# design.net
KiCad netlist of a schematic drawn in Altium Designer
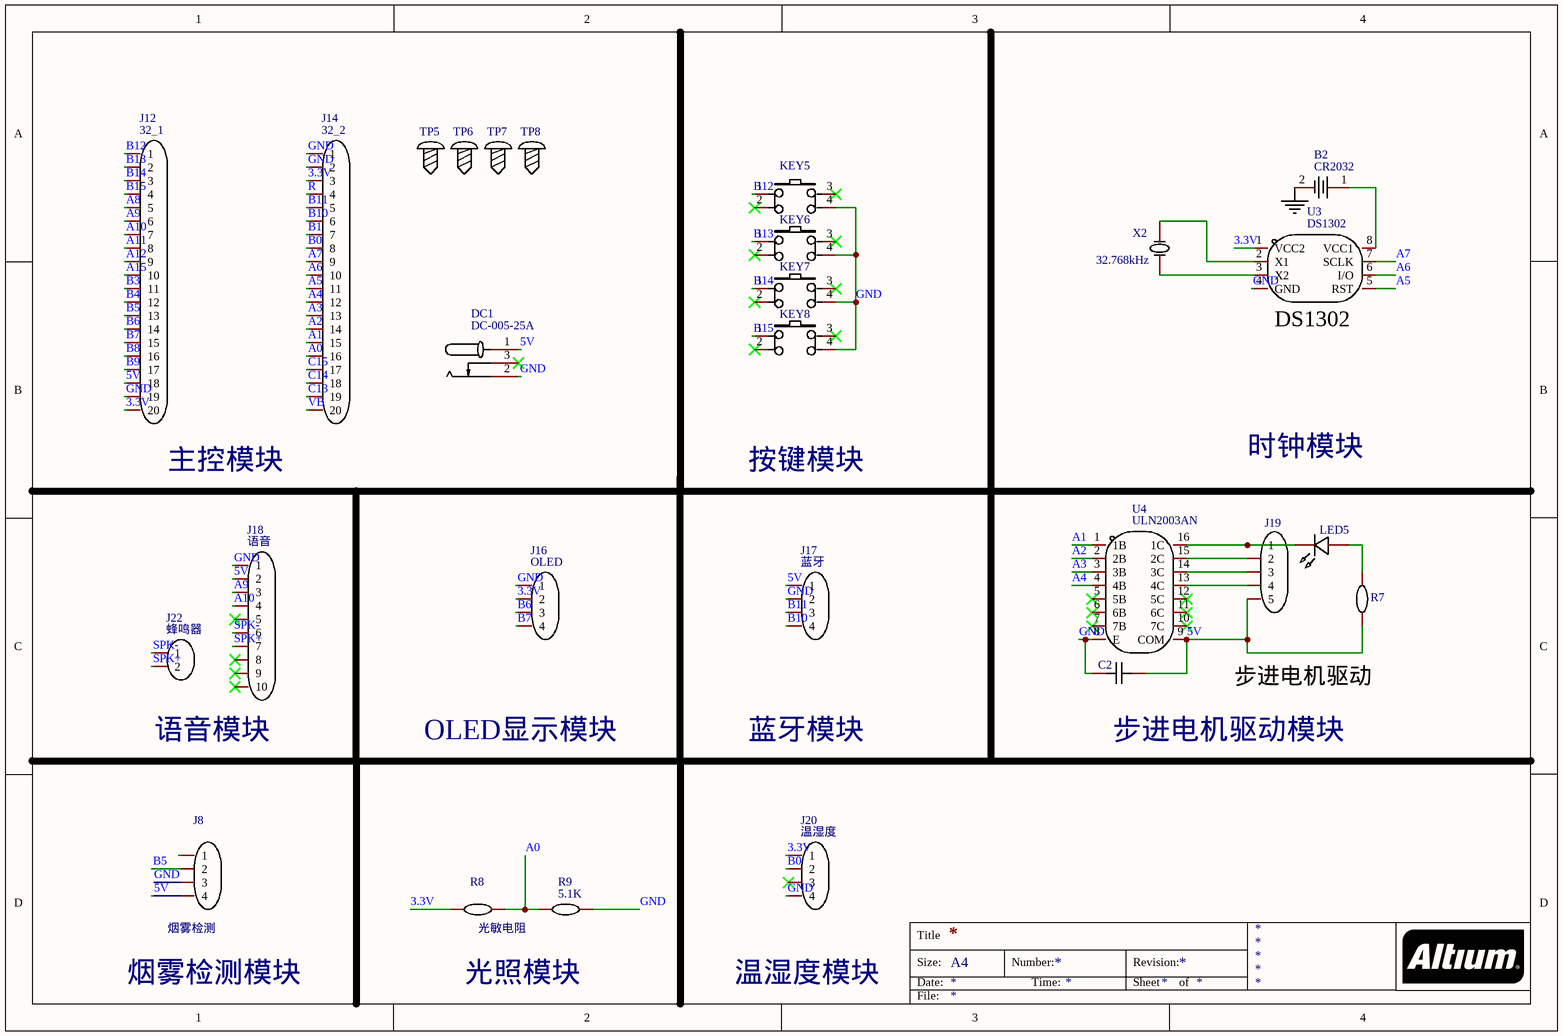
[diagram p0: 智能窗帘.schdoc]

(export (version "E")
  (design (tool "Eeschema 10.0.6"))
  (components
    (comp (ref "B2")
      (value "CR2032")
      (footprint "BAT-TH_BS-2-1")
      (fields
        (field (name "NAME") "CR2032")
        (field (name "MANUFACTURER") "Q&J")
        (field (name "MANUFACTURER PART") "BS-2-1")
      )
      (libsource (lib "altium-import") (part "root_2_BS-2-1_"))
    )
    (comp (ref "C2")
      (value "100nF")
      (footprint "CAP-TH_L5.5-W2.5-P5.00-D1.0")
      (fields
        (field (name "MANUFACTURER") "SHM(南方宏明)")
        (field (name "MANUFACTURER PART") "CCT104KC6X7RF5FH5A0")
      )
      (libsource (lib "altium-import") (part "root_0_CCT104KC6X7RF5FH5A0_"))
    )
    (comp (ref "DC1")
      (value "DC-005-25A")
      (footprint "DC-IN-TH_DC005")
      (fields (field (name "NAME") "DC-005-25A") (field (name "MANUFACTURER") "HRO"))
      (libsource (lib "altium-import") (part "root_0_DC-005-25A_"))
    )
    (comp (ref "J8")
      (value "温湿度")
      (footprint "HDR-M-2.54_1X4")
      (fields (field (name "NAME") "烟雾检测"))
      (libsource (lib "altium-import") (part "root_0_温湿度_"))
    )
    (comp (ref "J12")
      (value "32_1")
      (footprint "HDR-M-2.54_1X20")
      (fields (field (name "NAME") "32_1"))
      (libsource (lib "altium-import") (part "root_0_32_1_"))
    )
    (comp (ref "J14")
      (value "32_2")
      (footprint "HDR-M-2.54_1X20")
      (fields (field (name "NAME") "32_2"))
      (libsource (lib "altium-import") (part "root_0_32_2_"))
    )
    (comp (ref "J16")
      (value "OLED")
      (footprint "HDR-M-2.54_1X4")
      (fields (field (name "NAME") "OLED"))
      (libsource (lib "altium-import") (part "root_0_OLED_"))
    )
    (comp (ref "J17")
      (value "蓝牙")
      (footprint "HDR-M-2.54_1X4")
      (fields (field (name "NAME") "蓝牙"))
      (libsource (lib "altium-import") (part "root_0_蓝牙_"))
    )
    (comp (ref "J18")
      (value "语音")
      (footprint "HDR-M-2.54_1X10")
      (fields (field (name "NAME") "语音"))
      (libsource (lib "altium-import") (part "root_0_语音_"))
    )
    (comp (ref "J19")
      (value "HDR-M-2.54_1x5")
      (footprint "HDR-M-2.54_1X5")
      (libsource (lib "altium-import") (part "root_0_HDR-M-2.54_1x5_"))
    )
    (comp (ref "J20")
      (value "温湿度")
      (footprint "HDR-M-2.54_1X4")
      (fields (field (name "NAME") "温湿度"))
      (libsource (lib "altium-import") (part "root_0_温湿度_"))
    )
    (comp (ref "J22")
      (value "蜂鸣器")
      (footprint "HDR-M-2.54_1X2")
      (fields (field (name "NAME") "蜂鸣器"))
      (libsource (lib "altium-import") (part "root_0_蜂鸣器_"))
    )
    (comp (ref "KEY5")
      (value "6*6*9")
      (footprint "KEY-TH_4P-L6.0-W6.0-P4.50")
      (fields (field (name "MANUFACTURER") "ReliaPro"))
      (libsource (lib "altium-import") (part "root_0_6*6*9_"))
    )
    (comp (ref "KEY6")
      (value "6*6*9")
      (footprint "KEY-TH_4P-L6.0-W6.0-P4.50")
      (fields (field (name "MANUFACTURER") "ReliaPro"))
      (libsource (lib "altium-import") (part "root_0_6*6*9_"))
    )
    (comp (ref "KEY7")
      (value "6*6*9")
      (footprint "KEY-TH_4P-L6.0-W6.0-P4.50")
      (fields (field (name "MANUFACTURER") "ReliaPro"))
      (libsource (lib "altium-import") (part "root_0_6*6*9_"))
    )
    (comp (ref "KEY8")
      (value "6*6*9")
      (footprint "KEY-TH_4P-L6.0-W6.0-P4.50")
      (fields (field (name "MANUFACTURER") "ReliaPro"))
      (libsource (lib "altium-import") (part "root_0_6*6*9_"))
    )
    (comp (ref "LED5")
      (value "LED-TH-3mm_R")
      (footprint "LED-TH_BD3.0_RED")
      (fields
        (field (name "MANUFACTURER") "EVERLIGHT(台湾亿光)")
        (field (name "MANUFACTURER PART") "204-10SDRD/S530-A3-L")
      )
      (libsource (lib "altium-import") (part "root_2_204-10SDRD/S530-A3-L_"))
    )
    (comp (ref "R7")
      (value "0.5")
      (footprint "RES-TH_BD1.9-L3.3-P7.30-D0.5")
      (fields (field (name "MANUFACTURER") "CCO") (field (name "MANUFACTURER PART") "CF1/6W-0.5Ω±5% T52"))
      (libsource (lib "altium-import") (part "root_3_CF1/6W-0.5Ω±5% T52_"))
    )
    (comp (ref "R8")
      (value "光敏电阻")
      (footprint "RES-TH_BD2.5-L4.7-P8.70-D0.5")
      (fields
        (field (name "NAME") "光敏电阻")
        (field (name "MANUFACTURER") "TA-I Tech")
        (field (name "MANUFACTURER PART") "RN16T51001F")
      )
      (libsource (lib "altium-import") (part "root_0_RN16T51001F_"))
    )
    (comp (ref "R9")
      (value "5.1K")
      (footprint "RES-TH_BD2.5-L4.7-P8.70-D0.5")
      (fields
        (field (name "NAME") "5.1K")
        (field (name "MANUFACTURER") "TA-I Tech")
        (field (name "MANUFACTURER PART") "RN16T51001F")
      )
      (libsource (lib "altium-import") (part "root_0_RN16T51001F_"))
    )
    (comp (ref "TP5")
      (value "M3x6+4")
      (footprint "M3铜柱")
      (libsource (lib "altium-import") (part "root_0_M3x6+4_"))
    )
    (comp (ref "TP6")
      (value "M3x6+4")
      (footprint "M3铜柱")
      (libsource (lib "altium-import") (part "root_0_M3x6+4_"))
    )
    (comp (ref "TP7")
      (value "M3x6+4")
      (footprint "M3铜柱")
      (libsource (lib "altium-import") (part "root_0_M3x6+4_"))
    )
    (comp (ref "TP8")
      (value "M3x6+4")
      (footprint "M3铜柱")
      (libsource (lib "altium-import") (part "root_0_M3x6+4_"))
    )
    (comp (ref "U3")
      (value "DS1302")
      (footprint "DIP-8_L9.7-W6.4-P2.54-LS7.6-BL")
      (fields
        (field (name "NAME") "DS1302")
        (field (name "MANUFACTURER") "HGSEMI")
        (field (name "MANUFACTURER PART") "DS1302N")
      )
      (libsource (lib "altium-import") (part "root_0_DS1302N_"))
    )
    (comp (ref "U4")
      (value "ULN2003AN")
      (footprint "DIP-16_L19.8-W6.5-P2.54-LS7.6-BL")
      (fields (field (name "NAME") "ULN2003AN") (field (name "MANUFACTURER") "HTC Korea TAEJIN Tech"))
      (libsource (lib "altium-import") (part "root_0_ULN2003AN_"))
    )
    (comp (ref "X2")
      (value "32.768kHz")
      (footprint "OSC-TH_BD2.0-P0.70-D0.3")
      (fields
        (field (name "NAME") "32.768kHz")
        (field (name "MANUFACTURER") "LIMING(利明)")
        (field (name "MANUFACTURER PART") "26S-32.768-12.5-10-10/B")
      )
      (libsource (lib "altium-import") (part "root_1_26S-32.768-12.5-10-10/B_"))
    )
  )
  (nets
    (net (code "1") (name "/3.3V") (class "Default")
      (node (ref "J12") (pin "20") (pinfunction "20_20") (pintype "passive"))
      (node (ref "J14") (pin "3") (pinfunction "3_3") (pintype "passive"))
      (node (ref "J16") (pin "2") (pinfunction "2_2") (pintype "passive"))
      (node (ref "J20") (pin "1") (pinfunction "1_1") (pintype "passive"))
      (node (ref "R8") (pin "1") (pinfunction "1_1") (pintype "passive"))
      (node (ref "U3") (pin "1") (pinfunction "VCC2_1") (pintype "passive"))
    )
    (net (code "2") (name "/5V") (class "Default")
      (node (ref "C2") (pin "2") (pinfunction "2_2") (pintype "passive"))
      (node (ref "DC1") (pin "1") (pinfunction "1_1") (pintype "passive"))
      (node (ref "J12") (pin "18") (pinfunction "18_18") (pintype "passive"))
      (node (ref "J17") (pin "1") (pinfunction "1_1") (pintype "passive"))
      (node (ref "J18") (pin "2") (pinfunction "2_2") (pintype "passive"))
      (node (ref "J19") (pin "5") (pinfunction "5_5") (pintype "passive"))
      (node (ref "J8") (pin "4") (pinfunction "4_4") (pintype "passive"))
      (node (ref "R7") (pin "2") (pinfunction "2_2") (pintype "passive"))
      (node (ref "U4") (pin "9") (pinfunction "COM_9") (pintype "passive"))
    )
    (net (code "3") (name "/A0") (class "Default")
      (node (ref "J14") (pin "16") (pinfunction "16_16") (pintype "passive"))
      (node (ref "R8") (pin "2") (pinfunction "2_2") (pintype "passive"))
      (node (ref "R9") (pin "1") (pinfunction "1_1") (pintype "passive"))
    )
    (net (code "4") (name "/A1") (class "Default")
      (node (ref "J14") (pin "15") (pinfunction "15_15") (pintype "passive"))
      (node (ref "U4") (pin "1") (pinfunction "1B_1") (pintype "passive"))
    )
    (net (code "5") (name "/A2") (class "Default")
      (node (ref "J14") (pin "14") (pinfunction "14_14") (pintype "passive"))
      (node (ref "U4") (pin "2") (pinfunction "2B_2") (pintype "passive"))
    )
    (net (code "6") (name "/A3") (class "Default")
      (node (ref "J14") (pin "13") (pinfunction "13_13") (pintype "passive"))
      (node (ref "U4") (pin "3") (pinfunction "3B_3") (pintype "passive"))
    )
    (net (code "7") (name "/A4") (class "Default")
      (node (ref "J14") (pin "12") (pinfunction "12_12") (pintype "passive"))
      (node (ref "U4") (pin "4") (pinfunction "4B_4") (pintype "passive"))
    )
    (net (code "8") (name "/A5") (class "Default")
      (node (ref "J14") (pin "11") (pinfunction "11_11") (pintype "passive"))
      (node (ref "U3") (pin "5") (pinfunction "RST_5") (pintype "passive"))
    )
    (net (code "9") (name "/A6") (class "Default")
      (node (ref "J14") (pin "10") (pinfunction "10_10") (pintype "passive"))
      (node (ref "U3") (pin "6") (pinfunction "I/O_6") (pintype "passive"))
    )
    (net (code "10") (name "/A7") (class "Default")
      (node (ref "J14") (pin "9") (pinfunction "9_9") (pintype "passive"))
      (node (ref "U3") (pin "7") (pinfunction "SCLK_7") (pintype "passive"))
    )
    (net (code "11") (name "/A8") (class "Default")
      (node (ref "J12") (pin "5") (pinfunction "5_5") (pintype "passive"))
    )
    (net (code "12") (name "/A9") (class "Default")
      (node (ref "J12") (pin "6") (pinfunction "6_6") (pintype "passive"))
      (node (ref "J18") (pin "3") (pinfunction "3_3") (pintype "passive"))
    )
    (net (code "13") (name "/A10") (class "Default")
      (node (ref "J12") (pin "7") (pinfunction "7_7") (pintype "passive"))
      (node (ref "J18") (pin "4") (pinfunction "4_4") (pintype "passive"))
    )
    (net (code "14") (name "/A11") (class "Default")
      (node (ref "J12") (pin "8") (pinfunction "8_8") (pintype "passive"))
    )
    (net (code "15") (name "/A12") (class "Default")
      (node (ref "J12") (pin "9") (pinfunction "9_9") (pintype "passive"))
    )
    (net (code "16") (name "/A15") (class "Default")
      (node (ref "J12") (pin "10") (pinfunction "10_10") (pintype "passive"))
    )
    (net (code "17") (name "/B0") (class "Default")
      (node (ref "J14") (pin "8") (pinfunction "8_8") (pintype "passive"))
      (node (ref "J20") (pin "2") (pinfunction "2_2") (pintype "passive"))
    )
    (net (code "18") (name "/B1") (class "Default")
      (node (ref "J14") (pin "7") (pinfunction "7_7") (pintype "passive"))
    )
    (net (code "19") (name "/B3") (class "Default")
      (node (ref "J12") (pin "11") (pinfunction "11_11") (pintype "passive"))
    )
    (net (code "20") (name "/B4") (class "Default")
      (node (ref "J12") (pin "12") (pinfunction "12_12") (pintype "passive"))
    )
    (net (code "21") (name "/B5") (class "Default")
      (node (ref "J12") (pin "13") (pinfunction "13_13") (pintype "passive"))
      (node (ref "J8") (pin "2") (pinfunction "2_2") (pintype "passive"))
    )
    (net (code "22") (name "/B6") (class "Default")
      (node (ref "J12") (pin "14") (pinfunction "14_14") (pintype "passive"))
      (node (ref "J16") (pin "3") (pinfunction "3_3") (pintype "passive"))
    )
    (net (code "23") (name "/B7") (class "Default")
      (node (ref "J12") (pin "15") (pinfunction "15_15") (pintype "passive"))
      (node (ref "J16") (pin "4") (pinfunction "4_4") (pintype "passive"))
    )
    (net (code "24") (name "/B8") (class "Default")
      (node (ref "J12") (pin "16") (pinfunction "16_16") (pintype "passive"))
    )
    (net (code "25") (name "/B9") (class "Default")
      (node (ref "J12") (pin "17") (pinfunction "17_17") (pintype "passive"))
    )
    (net (code "26") (name "/B10") (class "Default")
      (node (ref "J14") (pin "6") (pinfunction "6_6") (pintype "passive"))
      (node (ref "J17") (pin "4") (pinfunction "4_4") (pintype "passive"))
    )
    (net (code "27") (name "/B11") (class "Default")
      (node (ref "J14") (pin "5") (pinfunction "5_5") (pintype "passive"))
      (node (ref "J17") (pin "3") (pinfunction "3_3") (pintype "passive"))
    )
    (net (code "28") (name "/B12") (class "Default")
      (node (ref "J12") (pin "1") (pinfunction "1_1") (pintype "passive"))
      (node (ref "KEY5") (pin "1") (pinfunction "1_1") (pintype "passive"))
    )
    (net (code "29") (name "/B13") (class "Default")
      (node (ref "J12") (pin "2") (pinfunction "2_2") (pintype "passive"))
      (node (ref "KEY6") (pin "1") (pinfunction "1_1") (pintype "passive"))
    )
    (net (code "30") (name "/B14") (class "Default")
      (node (ref "J12") (pin "3") (pinfunction "3_3") (pintype "passive"))
      (node (ref "KEY7") (pin "1") (pinfunction "1_1") (pintype "passive"))
    )
    (net (code "31") (name "/B15") (class "Default")
      (node (ref "J12") (pin "4") (pinfunction "4_4") (pintype "passive"))
      (node (ref "KEY8") (pin "1") (pinfunction "1_1") (pintype "passive"))
    )
    (net (code "32") (name "/C13") (class "Default")
      (node (ref "J14") (pin "19") (pinfunction "19_19") (pintype "passive"))
    )
    (net (code "33") (name "/C14") (class "Default")
      (node (ref "J14") (pin "18") (pinfunction "18_18") (pintype "passive"))
    )
    (net (code "34") (name "/C15") (class "Default")
      (node (ref "J14") (pin "17") (pinfunction "17_17") (pintype "passive"))
    )
    (net (code "35") (name "/R") (class "Default")
      (node (ref "J14") (pin "4") (pinfunction "4_4") (pintype "passive"))
    )
    (net (code "36") (name "/SPK+") (class "Default")
      (node (ref "J18") (pin "7") (pinfunction "7_7") (pintype "passive"))
      (node (ref "J22") (pin "2") (pinfunction "2_2") (pintype "passive"))
    )
    (net (code "37") (name "/SPK-") (class "Default")
      (node (ref "J18") (pin "6") (pinfunction "6_6") (pintype "passive"))
      (node (ref "J22") (pin "1") (pinfunction "1_1") (pintype "passive"))
    )
    (net (code "38") (name "/VB") (class "Default")
      (node (ref "J14") (pin "20") (pinfunction "20_20") (pintype "passive"))
    )
    (net (code "39") (name "GND") (class "Default")
      (node (ref "B2") (pin "2") (pinfunction "2_2") (pintype "passive"))
      (node (ref "C2") (pin "1") (pinfunction "1_1") (pintype "passive"))
      (node (ref "DC1") (pin "2") (pinfunction "2_2") (pintype "passive"))
      (node (ref "J12") (pin "19") (pinfunction "19_19") (pintype "passive"))
      (node (ref "J14") (pin "1") (pinfunction "1_1") (pintype "passive"))
      (node (ref "J14") (pin "2") (pinfunction "2_2") (pintype "passive"))
      (node (ref "J16") (pin "1") (pinfunction "1_1") (pintype "passive"))
      (node (ref "J17") (pin "2") (pinfunction "2_2") (pintype "passive"))
      (node (ref "J18") (pin "1") (pinfunction "1_1") (pintype "passive"))
      (node (ref "J20") (pin "4") (pinfunction "4_4") (pintype "passive"))
      (node (ref "J8") (pin "3") (pinfunction "3_3") (pintype "passive"))
      (node (ref "KEY5") (pin "4") (pinfunction "4_4") (pintype "passive"))
      (node (ref "KEY6") (pin "4") (pinfunction "4_4") (pintype "passive"))
      (node (ref "KEY7") (pin "4") (pinfunction "4_4") (pintype "passive"))
      (node (ref "KEY8") (pin "4") (pinfunction "4_4") (pintype "passive"))
      (node (ref "R9") (pin "2") (pinfunction "2_2") (pintype "passive"))
      (node (ref "U3") (pin "4") (pinfunction "GND_4") (pintype "passive"))
      (node (ref "U4") (pin "8") (pinfunction "E_8") (pintype "passive"))
    )
    (net (code "40") (name "Net-(LED5-Pad1)") (class "Default")
      (node (ref "LED5") (pin "1") (pinfunction "1_1") (pintype "passive"))
      (node (ref "R7") (pin "1") (pinfunction "1_1") (pintype "passive"))
    )
    (net (code "41") (name "Net-(U3-VCC1)") (class "Default")
      (node (ref "B2") (pin "1") (pinfunction "1_1") (pintype "passive"))
      (node (ref "U3") (pin "8") (pinfunction "VCC1_8") (pintype "passive"))
    )
    (net (code "42") (name "Net-(U3-X1)") (class "Default")
      (node (ref "U3") (pin "2") (pinfunction "X1_2") (pintype "passive"))
      (node (ref "X2") (pin "2") (pinfunction "OSC2_2") (pintype "passive"))
    )
    (net (code "43") (name "Net-(U3-X2)") (class "Default")
      (node (ref "U3") (pin "3") (pinfunction "X2_3") (pintype "passive"))
      (node (ref "X2") (pin "1") (pinfunction "OSC1_1") (pintype "passive"))
    )
    (net (code "44") (name "Net-(U4-1C)") (class "Default")
      (node (ref "J19") (pin "1") (pinfunction "1_1") (pintype "passive"))
      (node (ref "LED5") (pin "2") (pinfunction "2_2") (pintype "passive"))
      (node (ref "U4") (pin "16") (pinfunction "1C_16") (pintype "passive"))
    )
    (net (code "45") (name "Net-(U4-2C)") (class "Default")
      (node (ref "J19") (pin "2") (pinfunction "2_2") (pintype "passive"))
      (node (ref "U4") (pin "15") (pinfunction "2C_15") (pintype "passive"))
    )
    (net (code "46") (name "Net-(U4-3C)") (class "Default")
      (node (ref "J19") (pin "3") (pinfunction "3_3") (pintype "passive"))
      (node (ref "U4") (pin "14") (pinfunction "3C_14") (pintype "passive"))
    )
    (net (code "47") (name "Net-(U4-4C)") (class "Default")
      (node (ref "J19") (pin "4") (pinfunction "4_4") (pintype "passive"))
      (node (ref "U4") (pin "13") (pinfunction "4C_13") (pintype "passive"))
    )
    (net (code "48") (name "unconnected-(DC1-Pad3)") (class "Default")
      (node (ref "DC1") (pin "3") (pinfunction "3_3") (pintype "passive+no_connect"))
    )
    (net (code "49") (name "unconnected-(J8-Pad1)") (class "Default")
      (node (ref "J8") (pin "1") (pinfunction "1_1") (pintype "passive"))
    )
    (net (code "50") (name "unconnected-(J18-Pad5)") (class "Default")
      (node (ref "J18") (pin "5") (pinfunction "5_5") (pintype "passive+no_connect"))
    )
    (net (code "51") (name "unconnected-(J18-Pad8)") (class "Default")
      (node (ref "J18") (pin "8") (pinfunction "8_8") (pintype "passive+no_connect"))
    )
    (net (code "52") (name "unconnected-(J18-Pad9)") (class "Default")
      (node (ref "J18") (pin "9") (pinfunction "9_9") (pintype "passive+no_connect"))
    )
    (net (code "53") (name "unconnected-(J18-Pad10)") (class "Default")
      (node (ref "J18") (pin "10") (pinfunction "10_10") (pintype "passive+no_connect"))
    )
    (net (code "54") (name "unconnected-(J20-Pad3)") (class "Default")
      (node (ref "J20") (pin "3") (pinfunction "3_3") (pintype "passive+no_connect"))
    )
    (net (code "55") (name "unconnected-(KEY5-Pad2)") (class "Default")
      (node (ref "KEY5") (pin "2") (pinfunction "2_2") (pintype "passive+no_connect"))
    )
    (net (code "56") (name "unconnected-(KEY5-Pad3)") (class "Default")
      (node (ref "KEY5") (pin "3") (pinfunction "3_3") (pintype "passive+no_connect"))
    )
    (net (code "57") (name "unconnected-(KEY6-Pad2)") (class "Default")
      (node (ref "KEY6") (pin "2") (pinfunction "2_2") (pintype "passive+no_connect"))
    )
    (net (code "58") (name "unconnected-(KEY6-Pad3)") (class "Default")
      (node (ref "KEY6") (pin "3") (pinfunction "3_3") (pintype "passive+no_connect"))
    )
    (net (code "59") (name "unconnected-(KEY7-Pad2)") (class "Default")
      (node (ref "KEY7") (pin "2") (pinfunction "2_2") (pintype "passive+no_connect"))
    )
    (net (code "60") (name "unconnected-(KEY7-Pad3)") (class "Default")
      (node (ref "KEY7") (pin "3") (pinfunction "3_3") (pintype "passive+no_connect"))
    )
    (net (code "61") (name "unconnected-(KEY8-Pad2)") (class "Default")
      (node (ref "KEY8") (pin "2") (pinfunction "2_2") (pintype "passive+no_connect"))
    )
    (net (code "62") (name "unconnected-(KEY8-Pad3)") (class "Default")
      (node (ref "KEY8") (pin "3") (pinfunction "3_3") (pintype "passive+no_connect"))
    )
    (net (code "63") (name "unconnected-(U4-5B-Pad5)") (class "Default")
      (node (ref "U4") (pin "5") (pinfunction "5B_5") (pintype "passive+no_connect"))
    )
    (net (code "64") (name "unconnected-(U4-5C-Pad12)") (class "Default")
      (node (ref "U4") (pin "12") (pinfunction "5C_12") (pintype "passive+no_connect"))
    )
    (net (code "65") (name "unconnected-(U4-6B-Pad6)") (class "Default")
      (node (ref "U4") (pin "6") (pinfunction "6B_6") (pintype "passive+no_connect"))
    )
    (net (code "66") (name "unconnected-(U4-6C-Pad11)") (class "Default")
      (node (ref "U4") (pin "11") (pinfunction "6C_11") (pintype "passive+no_connect"))
    )
    (net (code "67") (name "unconnected-(U4-7B-Pad7)") (class "Default")
      (node (ref "U4") (pin "7") (pinfunction "7B_7") (pintype "passive+no_connect"))
    )
    (net (code "68") (name "unconnected-(U4-7C-Pad10)") (class "Default")
      (node (ref "U4") (pin "10") (pinfunction "7C_10") (pintype "passive+no_connect"))
    )
  )
)
